# Final.net
KiCad netlist of a schematic drawn in EAGLE
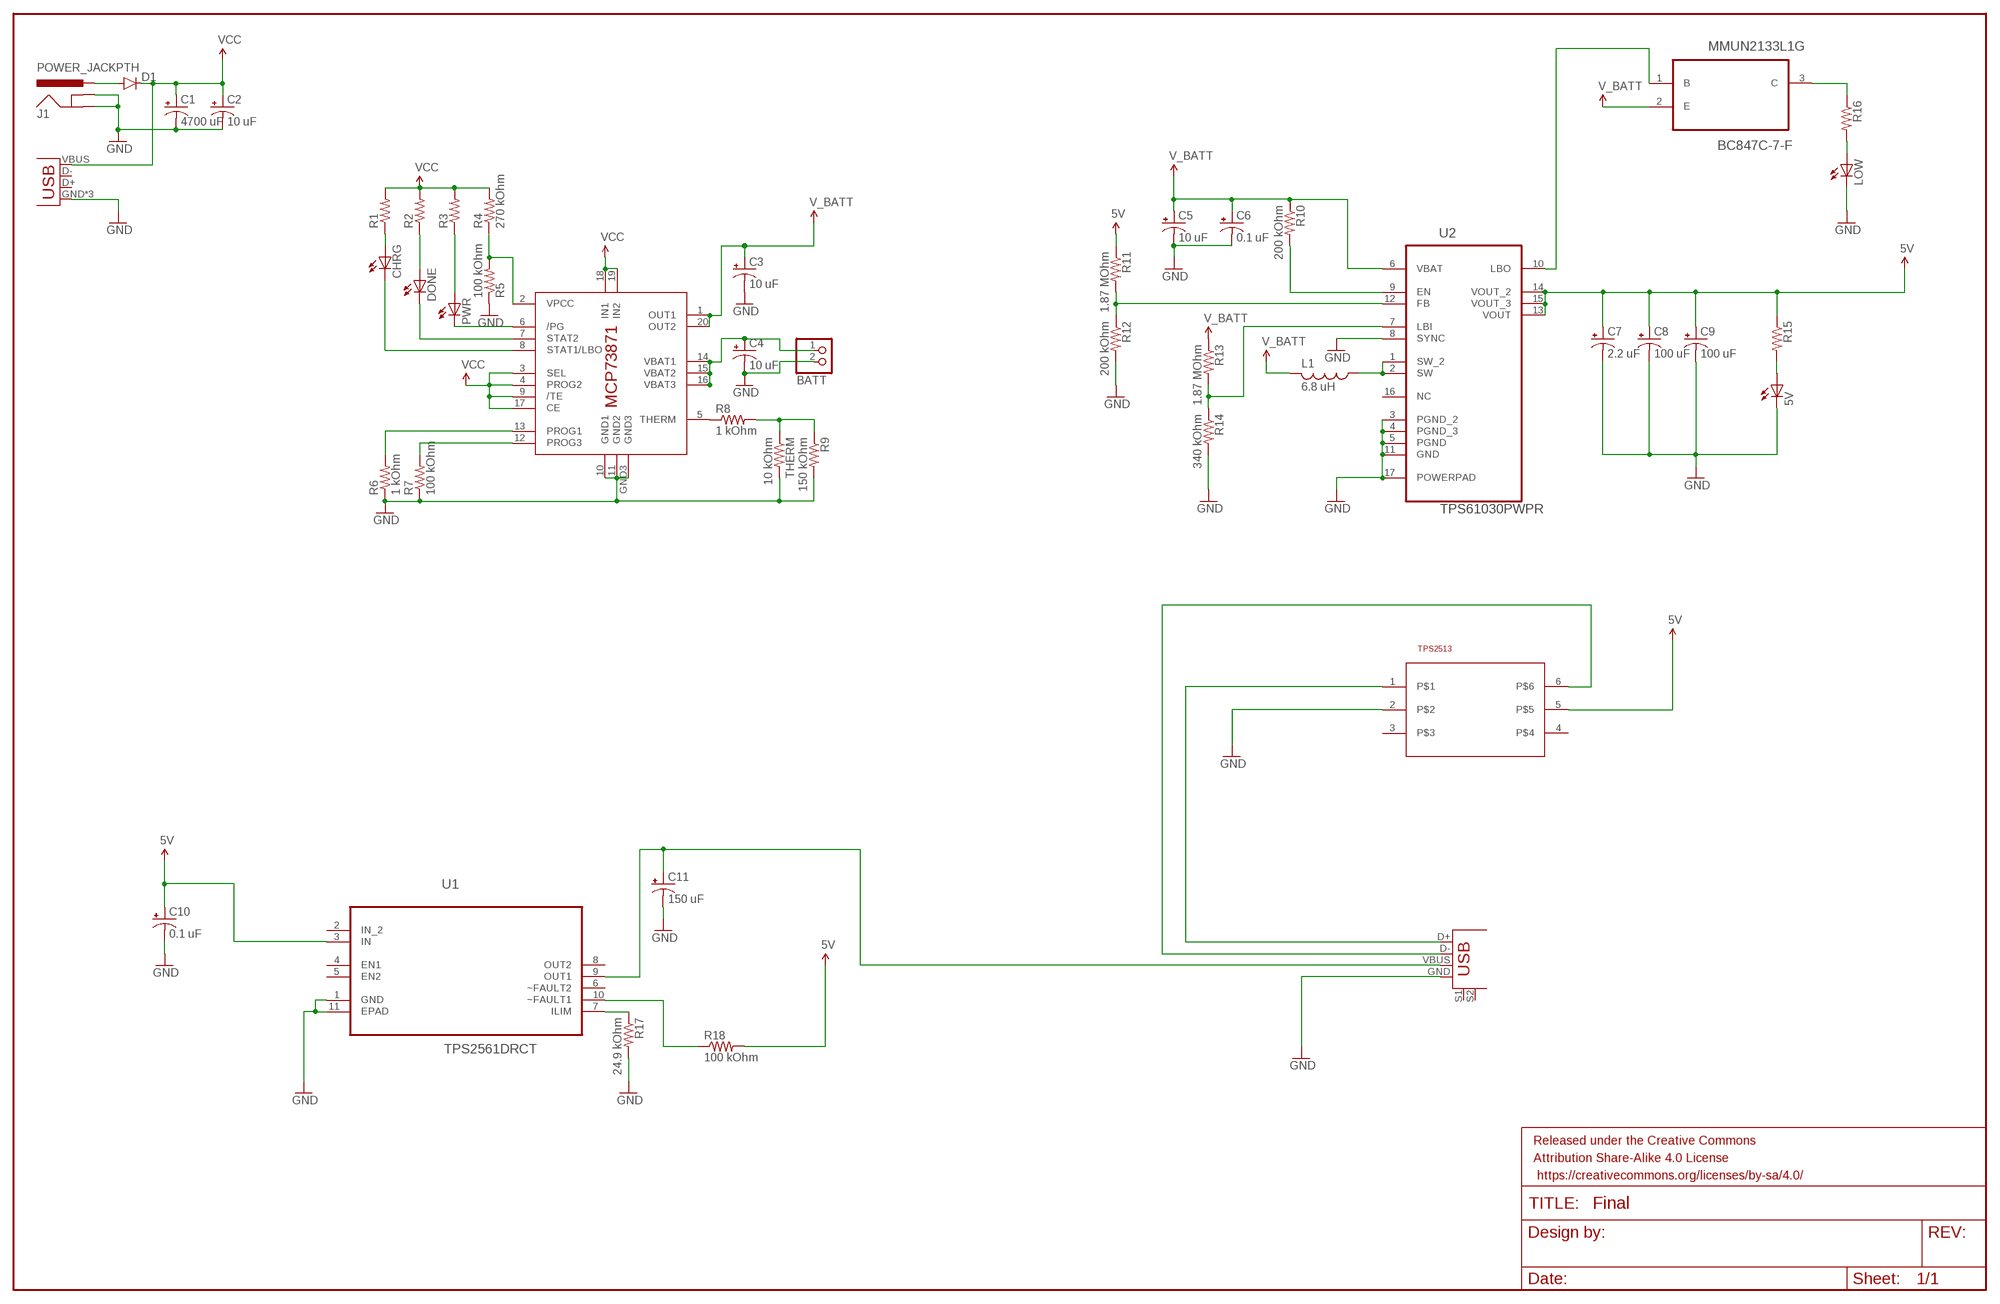
[diagram p0: schematic, sheet 1]

(export (version "E")
  (design (tool "Eeschema 10.0.6"))
  (components
    (comp (ref "5V")
      (value "LED5MM")
      (footprint "eagle-import:LED5MM")
      (libsource (lib "eagle-import") (part "LED5MM"))
    )
    (comp (ref "BATT")
      (value "JST_2PIN-SMT-RA")
      (footprint "eagle-import:JST-PH-2-SMT-RA")
      (libsource (lib "eagle-import") (part "JST_2PIN-SMT-RA"))
    )
    (comp (ref "C1")
      (value "4700 uF")
      (footprint "eagle-import:E7,5-16")
      (libsource (lib "eagle-import") (part "CPOL-USE7.5-16"))
    )
    (comp (ref "C2")
      (value "10 uF")
      (footprint "eagle-import:E2,5-5")
      (libsource (lib "eagle-import") (part "CPOL-USE2.5-5"))
    )
    (comp (ref "C3")
      (value "10 uF")
      (footprint "eagle-import:E2,5-5")
      (libsource (lib "eagle-import") (part "CPOL-USE2.5-5"))
    )
    (comp (ref "C4")
      (value "10 uF")
      (footprint "eagle-import:E2,5-5")
      (libsource (lib "eagle-import") (part "CPOL-USE2.5-5"))
    )
    (comp (ref "C5")
      (value "10 uF")
      (footprint "eagle-import:E2,5-5")
      (libsource (lib "eagle-import") (part "CPOL-USE2.5-5"))
    )
    (comp (ref "C6")
      (value "0.1 uF")
      (footprint "eagle-import:E2,5-5")
      (libsource (lib "eagle-import") (part "CPOL-USE2.5-5"))
    )
    (comp (ref "C7")
      (value "2.2 uF")
      (footprint "eagle-import:E2,5-5")
      (libsource (lib "eagle-import") (part "CPOL-USE2.5-5"))
    )
    (comp (ref "C8")
      (value "100 uF")
      (footprint "eagle-import:E2,5-5")
      (libsource (lib "eagle-import") (part "CPOL-USE2.5-5"))
    )
    (comp (ref "C9")
      (value "100 uF")
      (footprint "eagle-import:E2,5-5")
      (libsource (lib "eagle-import") (part "CPOL-USE2.5-5"))
    )
    (comp (ref "C10")
      (value "0.1 uF")
      (footprint "eagle-import:E2,5-5")
      (libsource (lib "eagle-import") (part "CPOL-USE2.5-5"))
    )
    (comp (ref "C11")
      (value "150 uF")
      (footprint "eagle-import:E2,5-5")
      (libsource (lib "eagle-import") (part "CPOL-USE2.5-5"))
    )
    (comp (ref "CHRG")
      (value "LED5MM")
      (footprint "eagle-import:LED5MM")
      (libsource (lib "eagle-import") (part "LED5MM"))
    )
    (comp (ref "D1")
      (value "DIODEPTH")
      (footprint "eagle-import:DIODE-1N4001")
      (libsource (lib "eagle-import") (part "DIODEPTH"))
    )
    (comp (ref "DONE")
      (value "LED5MM")
      (footprint "eagle-import:LED5MM")
      (libsource (lib "eagle-import") (part "LED5MM"))
    )
    (comp (ref "FRAME1")
      (value "FRAME-LEDGER")
      (footprint "eagle-import:CREATIVE_COMMONS")
      (libsource (lib "eagle-import") (part "FRAME-LEDGER"))
    )
    (comp (ref "IC1")
      (value "MCP73871")
      (footprint "eagle-import:QFN20")
      (libsource (lib "eagle-import") (part "MCP73871"))
    )
    (comp (ref "J1")
      (value "POWER_JACKPTH")
      (footprint "eagle-import:POWER_JACK_PTH")
      (libsource (lib "eagle-import") (part "POWER_JACKPTH"))
    )
    (comp (ref "L1")
      (value "6.8 uH")
      (footprint "eagle-import:LAL03")
      (libsource (lib "eagle-import") (part "L-USLAL03"))
    )
    (comp (ref "LOW")
      (value "LED5MM")
      (footprint "eagle-import:LED5MM")
      (libsource (lib "eagle-import") (part "LED5MM"))
    )
    (comp (ref "MMUN2133L1G")
      (value "BC847C-7-F")
      (footprint "eagle-import:SOT103P240X110-3N")
      (libsource (lib "eagle-import") (part "BC847C-7-F"))
    )
    (comp (ref "PWR")
      (value "LED5MM")
      (footprint "eagle-import:LED5MM")
      (libsource (lib "eagle-import") (part "LED5MM"))
    )
    (comp (ref "R1")
      (value "R-US_0207/10")
      (footprint "eagle-import:0207_10")
      (libsource (lib "eagle-import") (part "R-US_0207/10"))
    )
    (comp (ref "R2")
      (value "R-US_0207/10")
      (footprint "eagle-import:0207_10")
      (libsource (lib "eagle-import") (part "R-US_0207/10"))
    )
    (comp (ref "R3")
      (value "R-US_0207/10")
      (footprint "eagle-import:0207_10")
      (libsource (lib "eagle-import") (part "R-US_0207/10"))
    )
    (comp (ref "R4")
      (value "270 kOhm")
      (footprint "eagle-import:0207_10")
      (libsource (lib "eagle-import") (part "R-US_0207/10"))
    )
    (comp (ref "R5")
      (value "100 kOhm")
      (footprint "eagle-import:0207_10")
      (libsource (lib "eagle-import") (part "R-US_0207/10"))
    )
    (comp (ref "R6")
      (value "1 kOhm")
      (footprint "eagle-import:0207_10")
      (libsource (lib "eagle-import") (part "R-US_0207/10"))
    )
    (comp (ref "R7")
      (value "100 kOhm")
      (footprint "eagle-import:0207_10")
      (libsource (lib "eagle-import") (part "R-US_0207/10"))
    )
    (comp (ref "R8")
      (value "1 kOhm")
      (footprint "eagle-import:0207_10")
      (libsource (lib "eagle-import") (part "R-US_0207/10"))
    )
    (comp (ref "R9")
      (value "150 kOhm")
      (footprint "eagle-import:0207_10")
      (libsource (lib "eagle-import") (part "R-US_0207/10"))
    )
    (comp (ref "R10")
      (value "200 kOhm")
      (footprint "eagle-import:0207_10")
      (libsource (lib "eagle-import") (part "R-US_0207/10"))
    )
    (comp (ref "R11")
      (value "1.87 MOhm")
      (footprint "eagle-import:0207_10")
      (libsource (lib "eagle-import") (part "R-US_0207/10"))
    )
    (comp (ref "R12")
      (value "200 kOhm")
      (footprint "eagle-import:0207_10")
      (libsource (lib "eagle-import") (part "R-US_0207/10"))
    )
    (comp (ref "R13")
      (value "1.87 MOhm")
      (footprint "eagle-import:0207_10")
      (libsource (lib "eagle-import") (part "R-US_0207/10"))
    )
    (comp (ref "R14")
      (value "340 kOhm")
      (footprint "eagle-import:0207_10")
      (libsource (lib "eagle-import") (part "R-US_0207/10"))
    )
    (comp (ref "R15")
      (value "R-US_0207/10")
      (footprint "eagle-import:0207_10")
      (libsource (lib "eagle-import") (part "R-US_0207/10"))
    )
    (comp (ref "R16")
      (value "R-US_0207/10")
      (footprint "eagle-import:0207_10")
      (libsource (lib "eagle-import") (part "R-US_0207/10"))
    )
    (comp (ref "R17")
      (value "24.9 kOhm")
      (footprint "eagle-import:0207_10")
      (libsource (lib "eagle-import") (part "R-US_0207/10"))
    )
    (comp (ref "R18")
      (value "100 kOhm")
      (footprint "eagle-import:0207_10")
      (libsource (lib "eagle-import") (part "R-US_0207/10"))
    )
    (comp (ref "THERM")
      (value "10 kOhm")
      (footprint "eagle-import:0207_10")
      (libsource (lib "eagle-import") (part "R-US_0207/10"))
    )
    (comp (ref "TPS2513")
      (value "TPS2513")
      (footprint "eagle-import:SOT23-6")
      (libsource (lib "eagle-import") (part "TPS2513"))
    )
    (comp (ref "U$1")
      (value "USB+SHIELDUSB-A-S-NOSILK-FEMALE")
      (footprint "eagle-import:USB-A-S-NOSILK-FEMALE")
      (libsource (lib "eagle-import") (part "USB+SHIELDUSB-A-S-NOSILK-FEMALE"))
    )
    (comp (ref "U1")
      (value "TPS2561DRCT")
      (footprint "eagle-import:SON50P300X300X100-11N")
      (libsource (lib "eagle-import") (part "TPS2561DRCT"))
    )
    (comp (ref "U2")
      (value "TPS61030PWPR")
      (footprint "eagle-import:SOP65P640X120-17N")
      (libsource (lib "eagle-import") (part "TPS61030PWPR"))
    )
    (comp (ref "U3")
      (value "USB-MICROB")
      (footprint "eagle-import:USB-MICROB")
      (libsource (lib "eagle-import") (part "USB-MICROB"))
    )
  )
  (nets
    (net (code "1") (name "/IN_2") (class "Default")
      (node (ref "U1") (pin "2") (pinfunction "IN_2_2") (pintype "power_in"))
    )
    (net (code "2") (name "5V") (class "Default")
      (node (ref "C10") (pin "+") (pinfunction "+_+") (pintype "passive"))
      (node (ref "C7") (pin "+") (pinfunction "+_+") (pintype "passive"))
      (node (ref "C8") (pin "+") (pinfunction "+_+") (pintype "passive"))
      (node (ref "C9") (pin "+") (pinfunction "+_+") (pintype "passive"))
      (node (ref "R11") (pin "1") (pinfunction "1_1") (pintype "passive"))
      (node (ref "R15") (pin "1") (pinfunction "1_1") (pintype "passive"))
      (node (ref "R18") (pin "2") (pinfunction "2_2") (pintype "passive"))
      (node (ref "TPS2513") (pin "5") (pinfunction "P$5_5") (pintype "bidirectional"))
      (node (ref "U1") (pin "3") (pinfunction "IN_3") (pintype "power_in"))
      (node (ref "U2") (pin "13") (pinfunction "VOUT_13") (pintype "output"))
      (node (ref "U2") (pin "14") (pinfunction "VOUT_2_14") (pintype "output"))
      (node (ref "U2") (pin "15") (pinfunction "VOUT_3_15") (pintype "output"))
    )
    (net (code "3") (name "GND") (class "Default")
      (node (ref "5V") (pin "K") (pinfunction "C_K") (pintype "passive"))
      (node (ref "BATT") (pin "2") (pinfunction "1_2") (pintype "passive"))
      (node (ref "C1") (pin "-") (pinfunction "-_-") (pintype "passive"))
      (node (ref "C10") (pin "-") (pinfunction "-_-") (pintype "passive"))
      (node (ref "C11") (pin "-") (pinfunction "-_-") (pintype "passive"))
      (node (ref "C2") (pin "-") (pinfunction "-_-") (pintype "passive"))
      (node (ref "C3") (pin "-") (pinfunction "-_-") (pintype "passive"))
      (node (ref "C4") (pin "-") (pinfunction "-_-") (pintype "passive"))
      (node (ref "C5") (pin "-") (pinfunction "-_-") (pintype "passive"))
      (node (ref "C6") (pin "-") (pinfunction "-_-") (pintype "passive"))
      (node (ref "C7") (pin "-") (pinfunction "-_-") (pintype "passive"))
      (node (ref "C8") (pin "-") (pinfunction "-_-") (pintype "passive"))
      (node (ref "C9") (pin "-") (pinfunction "-_-") (pintype "passive"))
      (node (ref "IC1") (pin "10") (pinfunction "GND1_10") (pintype "power_in"))
      (node (ref "IC1") (pin "11") (pinfunction "GND2_11") (pintype "power_in"))
      (node (ref "IC1") (pin "GND3") (pinfunction "GND3_GND3") (pintype "power_in"))
      (node (ref "J1") (pin "GND") (pinfunction "GND_GND") (pintype "bidirectional"))
      (node (ref "J1") (pin "GNDBREAK") (pinfunction "GNDBREAK_GNDBREAK") (pintype "bidirectional"))
      (node (ref "LOW") (pin "K") (pinfunction "C_K") (pintype "passive"))
      (node (ref "R12") (pin "2") (pinfunction "2_2") (pintype "passive"))
      (node (ref "R14") (pin "2") (pinfunction "2_2") (pintype "passive"))
      (node (ref "R17") (pin "2") (pinfunction "2_2") (pintype "passive"))
      (node (ref "R5") (pin "1") (pinfunction "1_1") (pintype "passive"))
      (node (ref "R6") (pin "1") (pinfunction "1_1") (pintype "passive"))
      (node (ref "R7") (pin "1") (pinfunction "1_1") (pintype "passive"))
      (node (ref "R9") (pin "2") (pinfunction "2_2") (pintype "passive"))
      (node (ref "THERM") (pin "2") (pinfunction "2_2") (pintype "passive"))
      (node (ref "TPS2513") (pin "2") (pinfunction "P$2_2") (pintype "bidirectional"))
      (node (ref "U$1") (pin "GND") (pinfunction "GND_GND") (pintype "bidirectional"))
      (node (ref "U1") (pin "1") (pinfunction "GND_1") (pintype "passive"))
      (node (ref "U1") (pin "11") (pinfunction "EPAD_11") (pintype "passive"))
      (node (ref "U2") (pin "11") (pinfunction "GND_11") (pintype "passive"))
      (node (ref "U2") (pin "17") (pinfunction "POWERPAD_17") (pintype "passive"))
      (node (ref "U2") (pin "3") (pinfunction "PGND_2_3") (pintype "passive"))
      (node (ref "U2") (pin "4") (pinfunction "PGND_3_4") (pintype "passive"))
      (node (ref "U2") (pin "5") (pinfunction "PGND_5") (pintype "passive"))
      (node (ref "U2") (pin "8") (pinfunction "SYNC_8") (pintype "input"))
      (node (ref "U3") (pin "GND") (pinfunction "GND_GND") (pintype "bidirectional"))
      (node (ref "U3") (pin "MT1") (pinfunction "GND_MT1") (pintype "bidirectional"))
      (node (ref "U3") (pin "MT2") (pinfunction "GND_MT2") (pintype "bidirectional"))
    )
    (net (code "4") (name "Net-(5V-PadA)") (class "Default")
      (node (ref "5V") (pin "A") (pinfunction "A_A") (pintype "passive"))
      (node (ref "R15") (pin "2") (pinfunction "2_2") (pintype "passive"))
    )
    (net (code "5") (name "Net-(BATT-2)") (class "Default")
      (node (ref "BATT") (pin "1") (pinfunction "2_1") (pintype "passive"))
      (node (ref "C4") (pin "+") (pinfunction "+_+") (pintype "passive"))
      (node (ref "IC1") (pin "14") (pinfunction "VBAT1_14") (pintype "output"))
      (node (ref "IC1") (pin "15") (pinfunction "VBAT2_15") (pintype "output"))
      (node (ref "IC1") (pin "16") (pinfunction "VBAT3_16") (pintype "output"))
    )
    (net (code "6") (name "Net-(CHRG-C)") (class "Default")
      (node (ref "CHRG") (pin "K") (pinfunction "C_K") (pintype "passive"))
      (node (ref "IC1") (pin "8") (pinfunction "STAT1/LBO_8") (pintype "output"))
    )
    (net (code "7") (name "Net-(CHRG-PadA)") (class "Default")
      (node (ref "CHRG") (pin "A") (pinfunction "A_A") (pintype "passive"))
      (node (ref "R1") (pin "1") (pinfunction "1_1") (pintype "passive"))
    )
    (net (code "8") (name "Net-(D1-PadA)") (class "Default")
      (node (ref "D1") (pin "A") (pinfunction "A_A") (pintype "passive"))
      (node (ref "J1") (pin "PWR") (pinfunction "PWR_PWR") (pintype "bidirectional"))
    )
    (net (code "9") (name "Net-(DONE-C)") (class "Default")
      (node (ref "DONE") (pin "K") (pinfunction "C_K") (pintype "passive"))
      (node (ref "IC1") (pin "7") (pinfunction "STAT2_7") (pintype "output"))
    )
    (net (code "10") (name "Net-(DONE-PadA)") (class "Default")
      (node (ref "DONE") (pin "A") (pinfunction "A_A") (pintype "passive"))
      (node (ref "R2") (pin "1") (pinfunction "1_1") (pintype "passive"))
    )
    (net (code "11") (name "Net-(IC1-PROG1)") (class "Default")
      (node (ref "IC1") (pin "13") (pinfunction "PROG1_13") (pintype "input"))
      (node (ref "R6") (pin "2") (pinfunction "2_2") (pintype "passive"))
    )
    (net (code "12") (name "Net-(IC1-PROG3)") (class "Default")
      (node (ref "IC1") (pin "12") (pinfunction "PROG3_12") (pintype "input"))
      (node (ref "R7") (pin "2") (pinfunction "2_2") (pintype "passive"))
    )
    (net (code "13") (name "Net-(IC1-THERM)") (class "Default")
      (node (ref "IC1") (pin "5") (pinfunction "THERM_5") (pintype "input"))
      (node (ref "R8") (pin "1") (pinfunction "1_1") (pintype "passive"))
    )
    (net (code "14") (name "Net-(IC1-VPCC)") (class "Default")
      (node (ref "IC1") (pin "2") (pinfunction "VPCC_2") (pintype "input"))
      (node (ref "R4") (pin "1") (pinfunction "1_1") (pintype "passive"))
      (node (ref "R5") (pin "2") (pinfunction "2_2") (pintype "passive"))
    )
    (net (code "15") (name "Net-(IC1-{slash}PG)") (class "Default")
      (node (ref "IC1") (pin "6") (pinfunction "/PG_6") (pintype "output"))
      (node (ref "PWR") (pin "K") (pinfunction "C_K") (pintype "passive"))
    )
    (net (code "16") (name "Net-(LOW-PadA)") (class "Default")
      (node (ref "LOW") (pin "A") (pinfunction "A_A") (pintype "passive"))
      (node (ref "R16") (pin "2") (pinfunction "2_2") (pintype "passive"))
    )
    (net (code "17") (name "Net-(MMUN2133L1G-B)") (class "Default")
      (node (ref "MMUN2133L1G") (pin "1") (pinfunction "B_1") (pintype "input"))
      (node (ref "U2") (pin "10") (pinfunction "LBO_10") (pintype "output"))
    )
    (net (code "18") (name "Net-(MMUN2133L1G-C)") (class "Default")
      (node (ref "MMUN2133L1G") (pin "3") (pinfunction "C_3") (pintype "output"))
      (node (ref "R16") (pin "1") (pinfunction "1_1") (pintype "passive"))
    )
    (net (code "19") (name "Net-(PWR-PadA)") (class "Default")
      (node (ref "PWR") (pin "A") (pinfunction "A_A") (pintype "passive"))
      (node (ref "R3") (pin "1") (pinfunction "1_1") (pintype "passive"))
    )
    (net (code "20") (name "Net-(R8-Pad2)") (class "Default")
      (node (ref "R8") (pin "2") (pinfunction "2_2") (pintype "passive"))
      (node (ref "R9") (pin "1") (pinfunction "1_1") (pintype "passive"))
      (node (ref "THERM") (pin "1") (pinfunction "1_1") (pintype "passive"))
    )
    (net (code "21") (name "Net-(TPS2513-P$1)") (class "Default")
      (node (ref "TPS2513") (pin "1") (pinfunction "P$1_1") (pintype "bidirectional"))
      (node (ref "U$1") (pin "D+") (pinfunction "D+_D+") (pintype "bidirectional"))
    )
    (net (code "22") (name "Net-(TPS2513-P$6)") (class "Default")
      (node (ref "TPS2513") (pin "6") (pinfunction "P$6_6") (pintype "bidirectional"))
      (node (ref "U$1") (pin "D-") (pinfunction "D-_D-") (pintype "bidirectional"))
    )
    (net (code "23") (name "Net-(U1-ILIM)") (class "Default")
      (node (ref "R17") (pin "1") (pinfunction "1_1") (pintype "passive"))
      (node (ref "U1") (pin "7") (pinfunction "ILIM_7") (pintype "output"))
    )
    (net (code "24") (name "Net-(U1-OUT1)") (class "Default")
      (node (ref "C11") (pin "+") (pinfunction "+_+") (pintype "passive"))
      (node (ref "U$1") (pin "VBUS") (pinfunction "VBUS_VBUS") (pintype "bidirectional"))
      (node (ref "U1") (pin "9") (pinfunction "OUT1_9") (pintype "output"))
    )
    (net (code "25") (name "Net-(U1-~{FAULT1})") (class "Default")
      (node (ref "R18") (pin "1") (pinfunction "1_1") (pintype "passive"))
      (node (ref "U1") (pin "10") (pinfunction "~{FAULT1}_10") (pintype "output"))
    )
    (net (code "26") (name "Net-(U2-EN)") (class "Default")
      (node (ref "R10") (pin "2") (pinfunction "2_2") (pintype "passive"))
      (node (ref "U2") (pin "9") (pinfunction "EN_9") (pintype "power_in"))
    )
    (net (code "27") (name "Net-(U2-FB)") (class "Default")
      (node (ref "R11") (pin "2") (pinfunction "2_2") (pintype "passive"))
      (node (ref "R12") (pin "1") (pinfunction "1_1") (pintype "passive"))
      (node (ref "U2") (pin "12") (pinfunction "FB_12") (pintype "input"))
    )
    (net (code "28") (name "Net-(U2-LBI)") (class "Default")
      (node (ref "R13") (pin "2") (pinfunction "2_2") (pintype "passive"))
      (node (ref "R14") (pin "1") (pinfunction "1_1") (pintype "passive"))
      (node (ref "U2") (pin "7") (pinfunction "LBI_7") (pintype "output"))
    )
    (net (code "29") (name "Net-(U2-SW)") (class "Default")
      (node (ref "L1") (pin "1") (pinfunction "1_1") (pintype "passive"))
      (node (ref "U2") (pin "1") (pinfunction "SW_2_1") (pintype "input"))
      (node (ref "U2") (pin "2") (pinfunction "SW_2") (pintype "input"))
    )
    (net (code "30") (name "VCC") (class "Default")
      (node (ref "C1") (pin "+") (pinfunction "+_+") (pintype "passive"))
      (node (ref "C2") (pin "+") (pinfunction "+_+") (pintype "passive"))
      (node (ref "D1") (pin "C") (pinfunction "C_C") (pintype "passive"))
      (node (ref "IC1") (pin "17") (pinfunction "CE_17") (pintype "input"))
      (node (ref "IC1") (pin "18") (pinfunction "IN1_18") (pintype "input"))
      (node (ref "IC1") (pin "19") (pinfunction "IN2_19") (pintype "input"))
      (node (ref "IC1") (pin "3") (pinfunction "SEL_3") (pintype "input"))
      (node (ref "IC1") (pin "4") (pinfunction "PROG2_4") (pintype "input"))
      (node (ref "IC1") (pin "9") (pinfunction "/TE_9") (pintype "input"))
      (node (ref "R1") (pin "2") (pinfunction "2_2") (pintype "passive"))
      (node (ref "R2") (pin "2") (pinfunction "2_2") (pintype "passive"))
      (node (ref "R3") (pin "2") (pinfunction "2_2") (pintype "passive"))
      (node (ref "R4") (pin "2") (pinfunction "2_2") (pintype "passive"))
      (node (ref "U3") (pin "VBUS") (pinfunction "VBUS_VBUS") (pintype "bidirectional"))
    )
    (net (code "31") (name "V_BATT") (class "Default")
      (node (ref "C3") (pin "+") (pinfunction "+_+") (pintype "passive"))
      (node (ref "C5") (pin "+") (pinfunction "+_+") (pintype "passive"))
      (node (ref "C6") (pin "+") (pinfunction "+_+") (pintype "passive"))
      (node (ref "IC1") (pin "1") (pinfunction "OUT1_1") (pintype "output"))
      (node (ref "IC1") (pin "20") (pinfunction "OUT2_20") (pintype "output"))
      (node (ref "L1") (pin "2") (pinfunction "2_2") (pintype "passive"))
      (node (ref "MMUN2133L1G") (pin "2") (pinfunction "E_2") (pintype "passive"))
      (node (ref "R10") (pin "1") (pinfunction "1_1") (pintype "passive"))
      (node (ref "R13") (pin "1") (pinfunction "1_1") (pintype "passive"))
      (node (ref "U2") (pin "6") (pinfunction "VBAT_6") (pintype "power_in"))
    )
    (net (code "32") (name "unconnected-(TPS2513-P$3-Pad3)") (class "Default")
      (node (ref "TPS2513") (pin "3") (pinfunction "P$3_3") (pintype "bidirectional"))
    )
    (net (code "33") (name "unconnected-(TPS2513-P$4-Pad4)") (class "Default")
      (node (ref "TPS2513") (pin "4") (pinfunction "P$4_4") (pintype "bidirectional"))
    )
    (net (code "34") (name "unconnected-(U$1-PadS1)") (class "Default")
      (node (ref "U$1") (pin "S1") (pinfunction "S1_S1") (pintype "bidirectional"))
    )
    (net (code "35") (name "unconnected-(U$1-PadS2)") (class "Default")
      (node (ref "U$1") (pin "S2") (pinfunction "S2_S2") (pintype "bidirectional"))
    )
    (net (code "36") (name "unconnected-(U1-EN1-Pad4)") (class "Default")
      (node (ref "U1") (pin "4") (pinfunction "EN1_4") (pintype "input"))
    )
    (net (code "37") (name "unconnected-(U1-EN2-Pad5)") (class "Default")
      (node (ref "U1") (pin "5") (pinfunction "EN2_5") (pintype "input"))
    )
    (net (code "38") (name "unconnected-(U1-OUT2-Pad8)") (class "Default")
      (node (ref "U1") (pin "8") (pinfunction "OUT2_8") (pintype "output"))
    )
    (net (code "39") (name "unconnected-(U1-~{FAULT2}-Pad6)") (class "Default")
      (node (ref "U1") (pin "6") (pinfunction "~{FAULT2}_6") (pintype "output"))
    )
    (net (code "40") (name "unconnected-(U2-NC-Pad16)") (class "Default")
      (node (ref "U2") (pin "16") (pinfunction "NC_16") (pintype "no_connect"))
    )
    (net (code "41") (name "unconnected-(U3-PadD+)") (class "Default")
      (node (ref "U3") (pin "D+") (pinfunction "D+_D+") (pintype "bidirectional"))
    )
    (net (code "42") (name "unconnected-(U3-PadD-)") (class "Default")
      (node (ref "U3") (pin "D-") (pinfunction "D-_D-") (pintype "bidirectional"))
    )
  )
)
